# FRONT-UNIT-3_5.net
KiCad netlist of a schematic drawn in Altium Designer
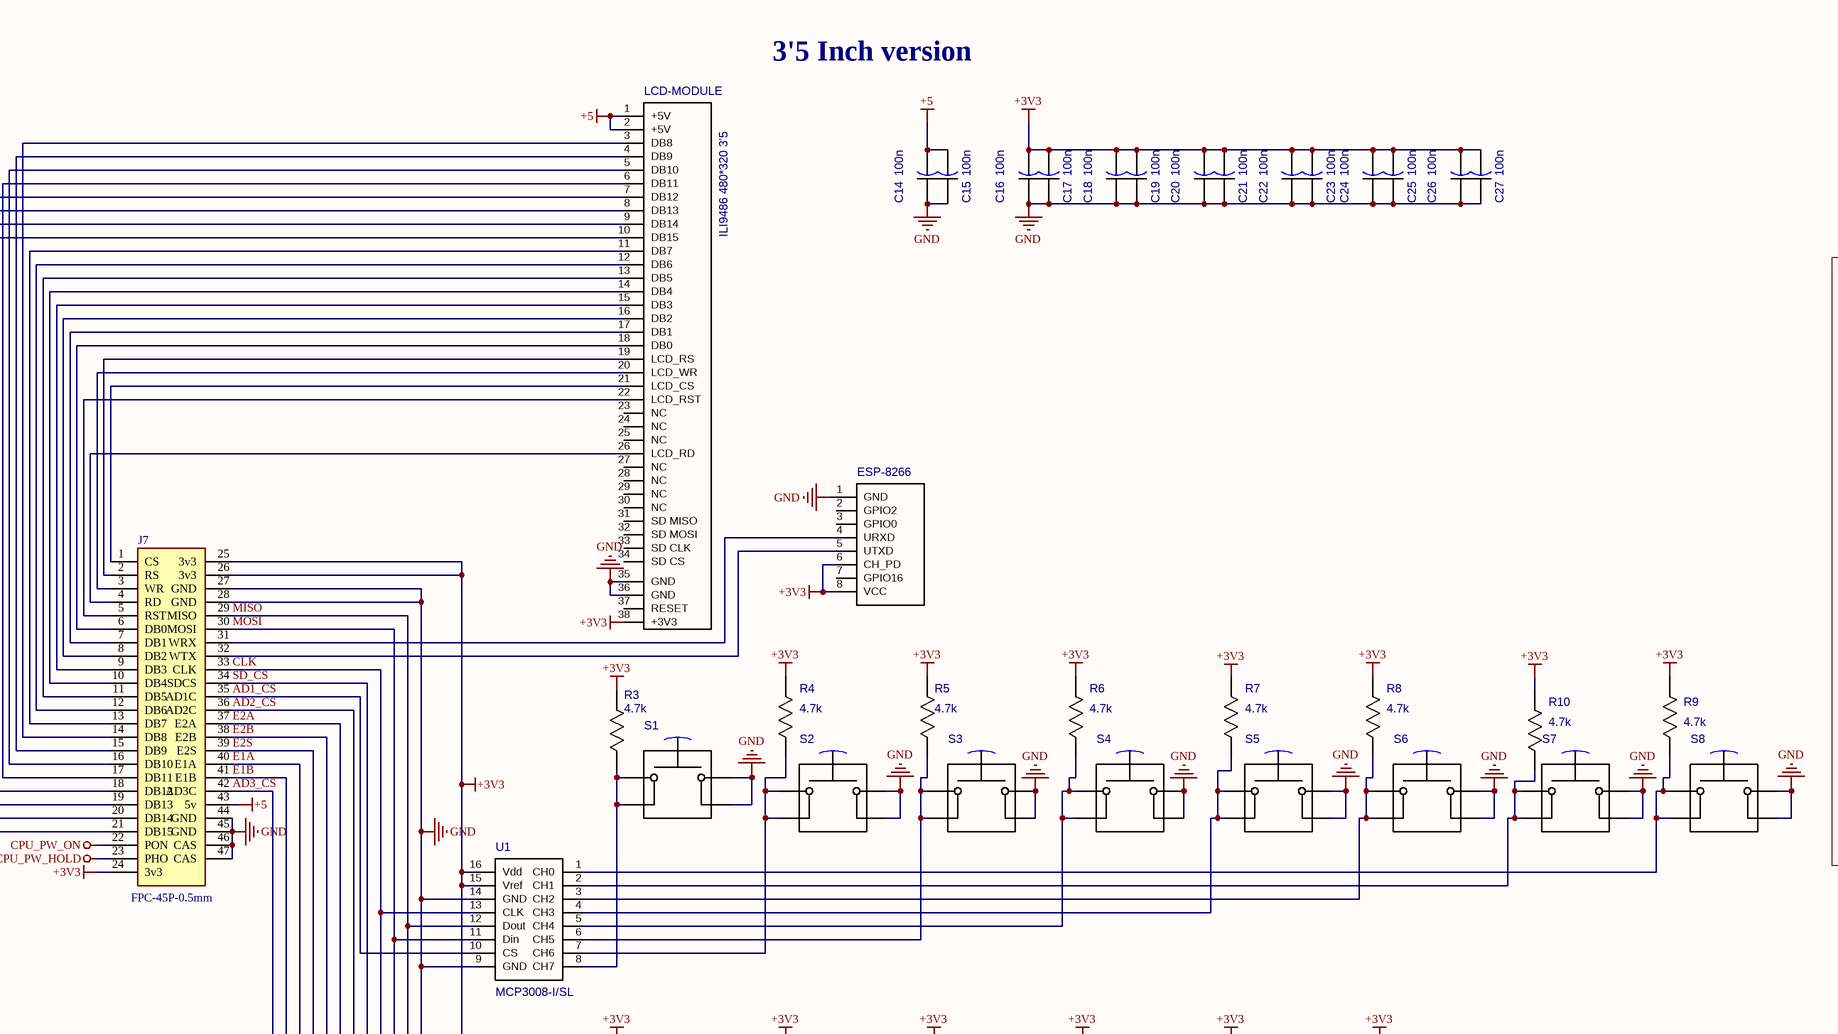
[diagram p0: FRONT-UNIT-3.5.SCHDOC, top left]
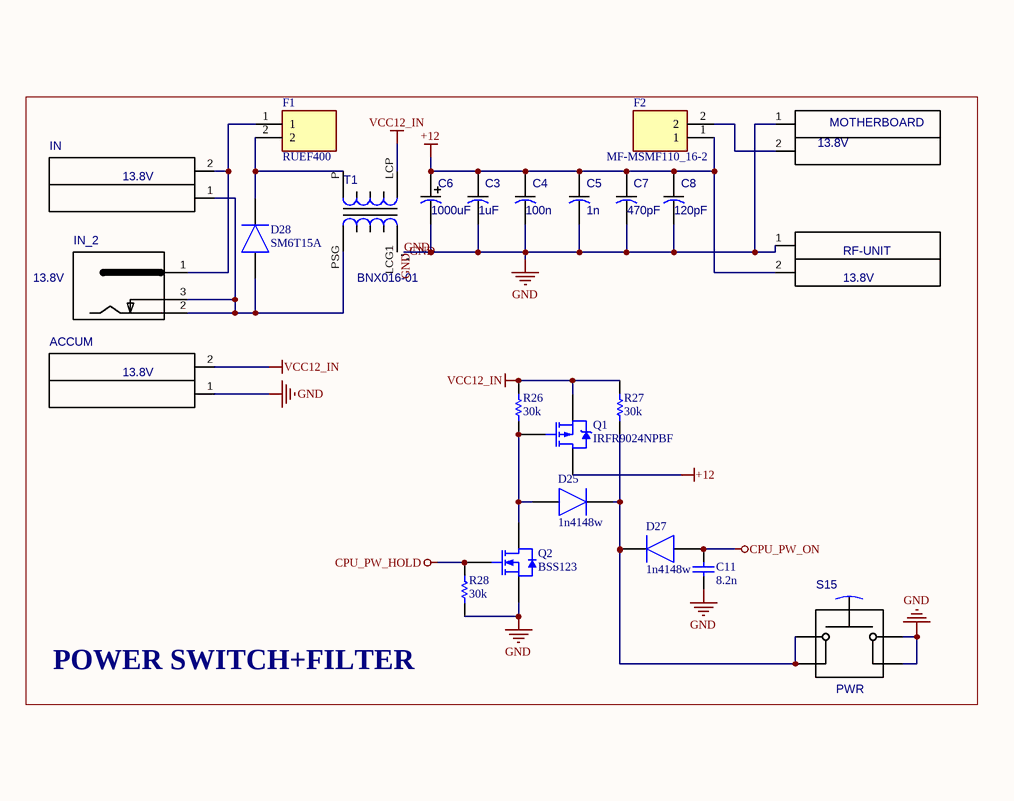
[diagram p1: FRONT-UNIT-3.5.SCHDOC, top right]
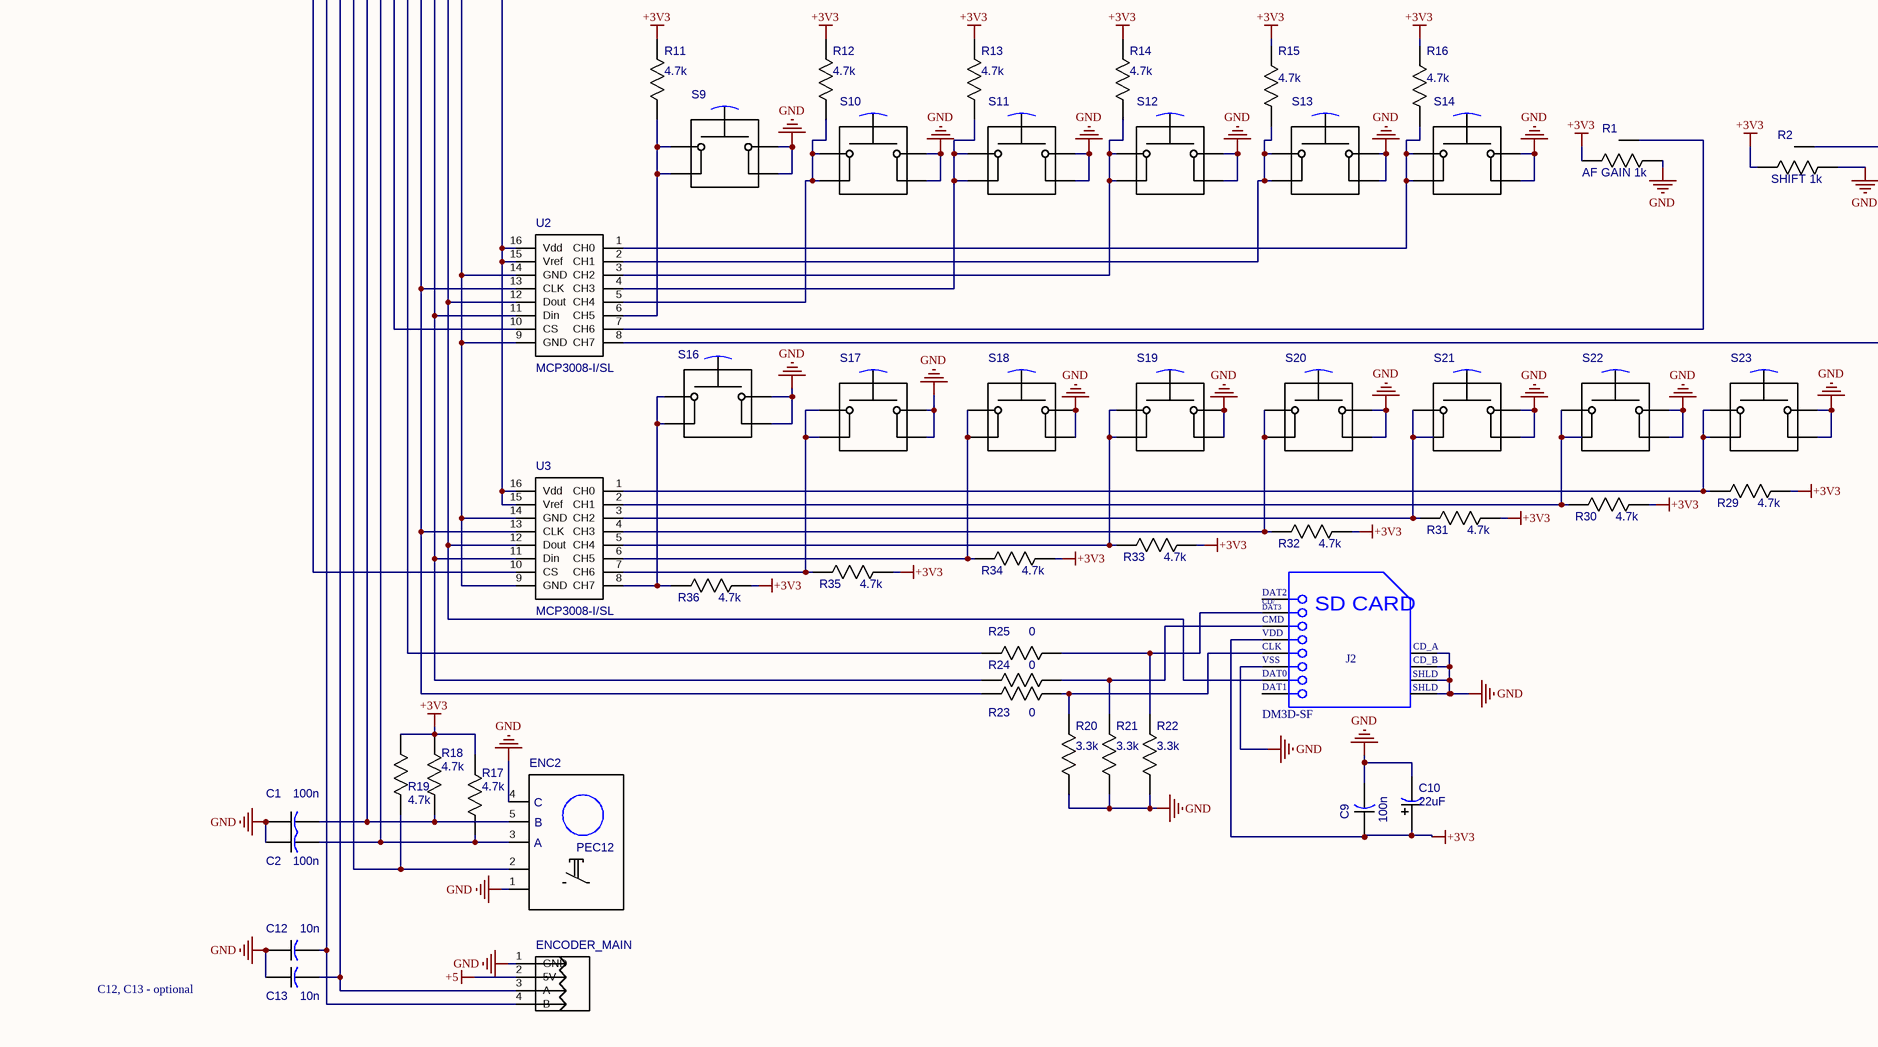
[diagram p2: FRONT-UNIT-3.5.SCHDOC, bottom left]
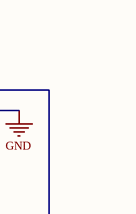
[diagram p3: FRONT-UNIT-3.5.SCHDOC, bottom right]

(export (version "E")
  (design (tool "Eeschema 10.0.6"))
  (components
    (comp (ref "ACCUM")
      (value "13.8V")
      (footprint "JX2")
      (description "JX2")
      (libsource (lib "*") (part "JX2"))
    )
    (comp (ref "C1")
      (value "100n")
      (footprint "CAP_0805")
      (description "CAP_0805")
      (libsource (lib "*") (part "CAP_0805"))
    )
    (comp (ref "C2")
      (value "100n")
      (footprint "CAP_0805")
      (description "CAP_0805")
      (libsource (lib "*") (part "CAP_0805"))
    )
    (comp (ref "C3")
      (value "1uF")
      (footprint "CAP_1206")
      (description "CAP_1206")
      (libsource (lib "*") (part "CAP_1206"))
    )
    (comp (ref "C4")
      (value "100n")
      (footprint "CAP_1206")
      (description "CAP_1206")
      (libsource (lib "*") (part "CAP_1206"))
    )
    (comp (ref "C5")
      (value "1n")
      (footprint "CAP_1206")
      (description "CAP_1206")
      (libsource (lib "*") (part "CAP_1206"))
    )
    (comp (ref "C6")
      (value "1000uF")
      (footprint "CAP250RP")
      (description "CAP250RP")
      (libsource (lib "*") (part "CAP250RP"))
    )
    (comp (ref "C7")
      (value "470pF")
      (footprint "CAP_1206")
      (description "CAP_1206")
      (libsource (lib "*") (part "CAP_1206"))
    )
    (comp (ref "C8")
      (value "120pF")
      (footprint "CAP_1206")
      (description "CAP_1206")
      (libsource (lib "*") (part "CAP_1206"))
    )
    (comp (ref "C9")
      (value "100n")
      (footprint "CAP_0805")
      (description "CAP_0805")
      (libsource (lib "*") (part "CAP_0805"))
    )
    (comp (ref "C10")
      (value "22uF")
      (footprint "EEEFC_sizeB")
      (description "EEEFC_sizeB")
      (libsource (lib "*") (part "EEEFC_sizeB"))
    )
    (comp (ref "C11")
      (value "8.2n")
      (footprint "CAPC2013X94X50LL20T25")
      (description "CAP_1206")
      (fields
        (field (name "MANUFACTURER") "AVX Interconnect / Elco")
        (field (name "PART NUMBER") "08055C822KAT2A")
      )
      (libsource (lib "Altium Content Vault") (part "CAP"))
    )
    (comp (ref "C12")
      (value "10n")
      (footprint "CAP_0805")
      (description "CAP_0805")
      (libsource (lib "*") (part "CAP_0805"))
    )
    (comp (ref "C13")
      (value "10n")
      (footprint "CAP_0805")
      (description "CAP_0805")
      (libsource (lib "*") (part "CAP_0805"))
    )
    (comp (ref "C14")
      (value "100n")
      (footprint "CAP_0805")
      (description "CAP_0805")
      (libsource (lib "*") (part "CAP_0805"))
    )
    (comp (ref "C15")
      (value "100n")
      (footprint "CAP_0805")
      (description "CAP_0805")
      (libsource (lib "*") (part "CAP_0805"))
    )
    (comp (ref "C16")
      (value "100n")
      (footprint "CAP_0805")
      (description "CAP_0805")
      (libsource (lib "*") (part "CAP_0805"))
    )
    (comp (ref "C17")
      (value "100n")
      (footprint "CAP_0805")
      (description "CAP_0805")
      (libsource (lib "*") (part "CAP_0805"))
    )
    (comp (ref "C18")
      (value "100n")
      (footprint "CAP_0805")
      (description "CAP_0805")
      (libsource (lib "*") (part "CAP_0805"))
    )
    (comp (ref "C19")
      (value "100n")
      (footprint "CAP_0805")
      (description "CAP_0805")
      (libsource (lib "*") (part "CAP_0805"))
    )
    (comp (ref "C20")
      (value "100n")
      (footprint "CAP_0805")
      (description "CAP_0805")
      (libsource (lib "*") (part "CAP_0805"))
    )
    (comp (ref "C21")
      (value "100n")
      (footprint "CAP_0805")
      (description "CAP_0805")
      (libsource (lib "*") (part "CAP_0805"))
    )
    (comp (ref "C22")
      (value "100n")
      (footprint "CAP_0805")
      (description "CAP_0805")
      (libsource (lib "*") (part "CAP_0805"))
    )
    (comp (ref "C23")
      (value "100n")
      (footprint "CAP_0805")
      (description "CAP_0805")
      (libsource (lib "*") (part "CAP_0805"))
    )
    (comp (ref "C24")
      (value "100n")
      (footprint "CAP_0805")
      (description "CAP_0805")
      (libsource (lib "*") (part "CAP_0805"))
    )
    (comp (ref "C25")
      (value "100n")
      (footprint "CAP_0805")
      (description "CAP_0805")
      (libsource (lib "*") (part "CAP_0805"))
    )
    (comp (ref "C26")
      (value "100n")
      (footprint "CAP_0805")
      (description "CAP_0805")
      (libsource (lib "*") (part "CAP_0805"))
    )
    (comp (ref "C27")
      (value "100n")
      (footprint "CAP_0805")
      (description "CAP_0805")
      (libsource (lib "*") (part "CAP_0805"))
    )
    (comp (ref "D25")
      (value "1n4148w")
      (footprint "SamacSys:SOD3716X135N")
      (description "Diode")
      (libsource (lib "*") (part "1n4148w"))
    )
    (comp (ref "D27")
      (value "1n4148w")
      (footprint "SamacSys:SOD3716X135N")
      (description "Diode")
      (libsource (lib "*") (part "1n4148w"))
    )
    (comp (ref "D28")
      (value "SM6T15A")
      (footprint "SamacSys:SMBJ36CATR")
      (description "Diode")
      (fields (field (name "MOUSER PART NUMBER") "511-SM6T15A") (field (name "RS PART NUMBER") "4864915P"))
      (libsource (lib "*") (part "SM6T15A"))
    )
    (comp (ref "ENC2") (value "PEC12") (footprint "PEC12") (libsource (lib "*") (part "PEC12")))
    (comp (ref "ENCODER_MAIN")
      (value "OPTICAL ENCODER")
      (footprint "644456-4")
      (libsource (lib "*") (part "644456-4"))
    )
    (comp (ref "ESP-8266")
      (value "ESP-01 ESP8266")
      (footprint "ESP-01 ESP8266")
      (libsource (lib "*") (part "ESP-01 ESP8266"))
    )
    (comp (ref "F1")
      (value "RUEF400")
      (footprint "SamacSys:RUEF400")
      (description "Fuse")
      (fields (field (name "MOUSER PART NUMBER") "650-RUEF400") (field (name "RS PART NUMBER") "5176837P"))
      (libsource (lib "*") (part "RUEF400"))
    )
    (comp (ref "F2")
      (value "MF-MSMF110_16-2")
      (footprint "SamacSys:FUSC4632X85N")
      (description "Fuse")
      (fields
        (field (name "MANUFACTURER_PART_NUMBER") "MF-MSMF110/16-2")
        (field (name "MOUSER PART NUMBER") "652-MF-MSMF110/16-2")
      )
      (libsource (lib "*") (part "MF-MSMF110_16-2"))
    )
    (comp (ref "IN") (value "13.8V") (footprint "JX2") (description "JX2") (libsource (lib "*") (part "JX2")))
    (comp (ref "IN_2")
      (value "13.8V")
      (footprint "PJ-050B")
      (description "PJ-050B")
      (libsource (lib "*") (part "PJ-050B"))
    )
    (comp (ref "J2")
      (value "DM3D-SF")
      (footprint "HIRO-DM3D-SF_V")
      (fields (field (name "MANUFACTURER") "Hirose Electric"))
      (libsource (lib "Altium Content Vault") (part "CN-SD-8-2SW-2S"))
    )
    (comp (ref "J7")
      (value "FPC-45P-0.5mm")
      (footprint "FRONT-UNIT-3.5:FH12S45S05SH60")
      (description "Connector")
      (fields
        (field (name "MANUFACTURER_PART_NUMBER") "FH12S-45S-0.5SH(55)")
        (field (name "MOUSER PART NUMBER") "798-FH12S-45S-05SH55")
      )
      (libsource (lib "*") (part "FH12S-45S-0.5SH_55_"))
    )
    (comp (ref "LCD-MODULE")
      (value "ILI9486 480*320 3'5")
      (footprint "LCD-MODULE-3.2-480-320")
      (description "LCD-MODULE_3'2_480х320")
      (libsource (lib "FRONT-UNIT") (part "LCD-MODULE_3'2_480х320"))
    )
    (comp (ref "MOTHERBOARD")
      (value "13.8V")
      (footprint "JX2")
      (description "JX2")
      (libsource (lib "*") (part "JX2"))
    )
    (comp (ref "Q1")
      (value "IRFR9024NPBF")
      (footprint "ONSC-DPAK-3-369C-01_V")
      (description "IRFR9024NPBF, Транзистор, Р-канал 55В 11А")
      (fields (field (name "MANUFACTURER") "On Semiconductor") (field (name "PARTNUMBER") "NTD2955G"))
      (libsource (lib "Altium Content Vault") (part "ONSC-PMOS-G1S3D4-3_B"))
    )
    (comp (ref "Q2")
      (value "BSS123")
      (footprint "FAIR-SOT23-3_V")
      (fields (field (name "MANUFACTURER") "Fairchild"))
      (libsource (lib "Altium Content Vault") (part "NEMOS-GSD-3"))
    )
    (comp (ref "R1")
      (value "AF GAIN 1k")
      (footprint "PTV09")
      (description "Adjustable Resistor PTV09")
      (fields (field (name "Comment") "ptv09a-4225f-b102"))
      (libsource (lib "*") (part "PTV09"))
    )
    (comp (ref "R2")
      (value "SHIFT 1k")
      (footprint "PTV09")
      (description "Adjustable Resistor PTV09")
      (fields (field (name "Comment") "ptv09a-4225f-b102"))
      (libsource (lib "*") (part "PTV09"))
    )
    (comp (ref "R3")
      (value "4.7k")
      (footprint "RES_0805")
      (description "RES_0805")
      (libsource (lib "*") (part "RES_0805"))
    )
    (comp (ref "R4")
      (value "4.7k")
      (footprint "RES_0805")
      (description "RES_0805")
      (libsource (lib "*") (part "RES_0805"))
    )
    (comp (ref "R5")
      (value "4.7k")
      (footprint "RES_0805")
      (description "RES_0805")
      (libsource (lib "*") (part "RES_0805"))
    )
    (comp (ref "R6")
      (value "4.7k")
      (footprint "RES_0805")
      (description "RES_0805")
      (libsource (lib "*") (part "RES_0805"))
    )
    (comp (ref "R7")
      (value "4.7k")
      (footprint "RES_0805")
      (description "RES_0805")
      (libsource (lib "*") (part "RES_0805"))
    )
    (comp (ref "R8")
      (value "4.7k")
      (footprint "RES_0805")
      (description "RES_0805")
      (libsource (lib "*") (part "RES_0805"))
    )
    (comp (ref "R9")
      (value "4.7k")
      (footprint "RES_0805")
      (description "RES_0805")
      (libsource (lib "*") (part "RES_0805"))
    )
    (comp (ref "R10")
      (value "4.7k")
      (footprint "RES_0805")
      (description "RES_0805")
      (libsource (lib "*") (part "RES_0805"))
    )
    (comp (ref "R11")
      (value "4.7k")
      (footprint "RES_0805")
      (description "RES_0805")
      (libsource (lib "*") (part "RES_0805"))
    )
    (comp (ref "R12")
      (value "4.7k")
      (footprint "RES_0805")
      (description "RES_0805")
      (libsource (lib "*") (part "RES_0805"))
    )
    (comp (ref "R13")
      (value "4.7k")
      (footprint "RES_0805")
      (description "RES_0805")
      (libsource (lib "*") (part "RES_0805"))
    )
    (comp (ref "R14")
      (value "4.7k")
      (footprint "RES_0805")
      (description "RES_0805")
      (libsource (lib "*") (part "RES_0805"))
    )
    (comp (ref "R15")
      (value "4.7k")
      (footprint "RES_0805")
      (description "RES_0805")
      (libsource (lib "*") (part "RES_0805"))
    )
    (comp (ref "R16")
      (value "4.7k")
      (footprint "RES_0805")
      (description "RES_0805")
      (libsource (lib "*") (part "RES_0805"))
    )
    (comp (ref "R17")
      (value "4.7k")
      (footprint "RES_0805")
      (description "RES_0805")
      (libsource (lib "*") (part "RES_0805"))
    )
    (comp (ref "R18")
      (value "4.7k")
      (footprint "RES_0805")
      (description "RES_0805")
      (libsource (lib "*") (part "RES_0805"))
    )
    (comp (ref "R19")
      (value "4.7k")
      (footprint "RES_0805")
      (description "RES_0805")
      (libsource (lib "*") (part "RES_0805"))
    )
    (comp (ref "R20")
      (value "3.3k")
      (footprint "RES_0805")
      (description "RES_0805")
      (libsource (lib "*") (part "RES_0805"))
    )
    (comp (ref "R21")
      (value "3.3k")
      (footprint "RES_0805")
      (description "RES_0805")
      (libsource (lib "*") (part "RES_0805"))
    )
    (comp (ref "R22")
      (value "3.3k")
      (footprint "RES_0805")
      (description "RES_0805")
      (libsource (lib "*") (part "RES_0805"))
    )
    (comp (ref "R23")
      (value "0")
      (footprint "RES_0805")
      (description "RES_0805")
      (libsource (lib "*") (part "RES_0805"))
    )
    (comp (ref "R24")
      (value "0")
      (footprint "RES_0805")
      (description "RES_0805")
      (libsource (lib "*") (part "RES_0805"))
    )
    (comp (ref "R25")
      (value "0")
      (footprint "RES_0805")
      (description "RES_0805")
      (libsource (lib "*") (part "RES_0805"))
    )
    (comp (ref "R26")
      (value "30k")
      (footprint "RESC2013X60X40NL20T25")
      (description "RES_0805")
      (fields (field (name "MANUFACTURER") "Panasonic") (field (name "PART NUMBER") "ERA-6AEB303V"))
      (libsource (lib "Altium Content Vault") (part "RES"))
    )
    (comp (ref "R27")
      (value "30k")
      (footprint "RESC2013X60X40NL20T25")
      (description "RES_0805")
      (fields (field (name "MANUFACTURER") "Panasonic") (field (name "PART NUMBER") "ERA-6AEB303V"))
      (libsource (lib "Altium Content Vault") (part "RES"))
    )
    (comp (ref "R28")
      (value "30k")
      (footprint "RESC2013X60X40NL20T25")
      (description "RES_0805")
      (fields (field (name "MANUFACTURER") "Panasonic") (field (name "PART NUMBER") "ERA-6AEB303V"))
      (libsource (lib "Altium Content Vault") (part "RES"))
    )
    (comp (ref "R29")
      (value "4.7k")
      (footprint "RES_0805")
      (description "RES_0805")
      (libsource (lib "*") (part "RES_0805"))
    )
    (comp (ref "R30")
      (value "4.7k")
      (footprint "RES_0805")
      (description "RES_0805")
      (libsource (lib "*") (part "RES_0805"))
    )
    (comp (ref "R31")
      (value "4.7k")
      (footprint "RES_0805")
      (description "RES_0805")
      (libsource (lib "*") (part "RES_0805"))
    )
    (comp (ref "R32")
      (value "4.7k")
      (footprint "RES_0805")
      (description "RES_0805")
      (libsource (lib "*") (part "RES_0805"))
    )
    (comp (ref "R33")
      (value "4.7k")
      (footprint "RES_0805")
      (description "RES_0805")
      (libsource (lib "*") (part "RES_0805"))
    )
    (comp (ref "R34")
      (value "4.7k")
      (footprint "RES_0805")
      (description "RES_0805")
      (libsource (lib "*") (part "RES_0805"))
    )
    (comp (ref "R35")
      (value "4.7k")
      (footprint "RES_0805")
      (description "RES_0805")
      (libsource (lib "*") (part "RES_0805"))
    )
    (comp (ref "R36")
      (value "4.7k")
      (footprint "RES_0805")
      (description "RES_0805")
      (libsource (lib "*") (part "RES_0805"))
    )
    (comp (ref "RF-UNIT")
      (value "13.8V")
      (footprint "JX2")
      (description "JX2")
      (libsource (lib "*") (part "JX2"))
    )
    (comp (ref "S1")
      (value "PTS645SK50LFS")
      (footprint "PTS645SK50LFS")
      (fields (field (name "LCSC PART #") "test"))
      (libsource (lib "*") (part "PTS645SK50LFS"))
    )
    (comp (ref "S2")
      (value "PTS645SK50LFS")
      (footprint "PTS645SK50LFS")
      (libsource (lib "*") (part "PTS645SK50LFS"))
    )
    (comp (ref "S3")
      (value "PTS645SK50LFS")
      (footprint "PTS645SK50LFS")
      (libsource (lib "*") (part "PTS645SK50LFS"))
    )
    (comp (ref "S4")
      (value "PTS645SK50LFS")
      (footprint "PTS645SK50LFS")
      (libsource (lib "*") (part "PTS645SK50LFS"))
    )
    (comp (ref "S5")
      (value "PTS645SK50LFS")
      (footprint "PTS645SK50LFS")
      (libsource (lib "*") (part "PTS645SK50LFS"))
    )
    (comp (ref "S6")
      (value "PTS645SK50LFS")
      (footprint "PTS645SK50LFS")
      (libsource (lib "*") (part "PTS645SK50LFS"))
    )
    (comp (ref "S7")
      (value "PTS645SK50LFS")
      (footprint "PTS645SK50LFS")
      (libsource (lib "*") (part "PTS645SK50LFS"))
    )
    (comp (ref "S8")
      (value "PTS645SK50LFS")
      (footprint "PTS645SK50LFS")
      (libsource (lib "*") (part "PTS645SK50LFS"))
    )
    (comp (ref "S9")
      (value "PTS645SK50LFS")
      (footprint "PTS645SK50LFS")
      (libsource (lib "*") (part "PTS645SK50LFS"))
    )
    (comp (ref "S10")
      (value "PTS645SK50LFS")
      (footprint "PTS645SK50LFS")
      (libsource (lib "*") (part "PTS645SK50LFS"))
    )
    (comp (ref "S11")
      (value "PTS645SK50LFS")
      (footprint "PTS645SK50LFS")
      (libsource (lib "*") (part "PTS645SK50LFS"))
    )
    (comp (ref "S12")
      (value "PTS645SK50LFS")
      (footprint "PTS645SK50LFS")
      (libsource (lib "*") (part "PTS645SK50LFS"))
    )
    (comp (ref "S13")
      (value "PTS645SK50LFS")
      (footprint "PTS645SK50LFS")
      (libsource (lib "*") (part "PTS645SK50LFS"))
    )
    (comp (ref "S14")
      (value "PTS645SK50LFS")
      (footprint "PTS645SK50LFS")
      (libsource (lib "*") (part "PTS645SK50LFS"))
    )
    (comp (ref "S15")
      (value "PWR")
      (footprint "PTS645SK50LFS")
      (description "PTS645SK50LFS")
      (libsource (lib "*") (part "PTS645SK50LFS"))
    )
    (comp (ref "S16")
      (value "PTS645SK50LFS")
      (footprint "PTS645SK50LFS")
      (libsource (lib "*") (part "PTS645SK50LFS"))
    )
    (comp (ref "S17")
      (value "PTS645SK50LFS")
      (footprint "PTS645SK50LFS")
      (libsource (lib "*") (part "PTS645SK50LFS"))
    )
    (comp (ref "S18")
      (value "PTS645SK50LFS")
      (footprint "PTS645SK50LFS")
      (libsource (lib "*") (part "PTS645SK50LFS"))
    )
    (comp (ref "S19")
      (value "PTS645SK50LFS")
      (footprint "PTS645SK50LFS")
      (libsource (lib "*") (part "PTS645SK50LFS"))
    )
    (comp (ref "S20")
      (value "PTS645SK50LFS")
      (footprint "PTS645SK50LFS")
      (libsource (lib "*") (part "PTS645SK50LFS"))
    )
    (comp (ref "S21")
      (value "PTS645SK50LFS")
      (footprint "PTS645SK50LFS")
      (libsource (lib "*") (part "PTS645SK50LFS"))
    )
    (comp (ref "S22")
      (value "PTS645SK50LFS")
      (footprint "PTS645SK50LFS")
      (libsource (lib "*") (part "PTS645SK50LFS"))
    )
    (comp (ref "S23")
      (value "PTS645SK50LFS")
      (footprint "PTS645SK50LFS")
      (libsource (lib "*") (part "PTS645SK50LFS"))
    )
    (comp (ref "T1")
      (value "BNX016-01")
      (footprint "TRANSF_ICORE")
      (libsource (lib "*") (part "TRANSF_ICORE"))
    )
    (comp (ref "U1")
      (value "MCP3008-I/SL")
      (footprint "MCP3008-I/SL")
      (libsource (lib "*") (part "MCP3008-I/SL"))
    )
    (comp (ref "U2")
      (value "MCP3008-I/SL")
      (footprint "MCP3008-I/SL")
      (libsource (lib "*") (part "MCP3008-I/SL"))
    )
    (comp (ref "U3")
      (value "MCP3008-I/SL")
      (footprint "MCP3008-I/SL")
      (libsource (lib "*") (part "MCP3008-I/SL"))
    )
  )
  (nets
    (net (code "1") (name "+3V3") (class "Default")
      (node (ref "C10") (pin "1") (pinfunction "PLUS_1") (pintype "passive"))
      (node (ref "C16") (pin "2") (pinfunction "2_2") (pintype "passive"))
      (node (ref "C17") (pin "2") (pinfunction "2_2") (pintype "passive"))
      (node (ref "C18") (pin "2") (pinfunction "2_2") (pintype "passive"))
      (node (ref "C19") (pin "2") (pinfunction "2_2") (pintype "passive"))
      (node (ref "C20") (pin "2") (pinfunction "2_2") (pintype "passive"))
      (node (ref "C21") (pin "2") (pinfunction "2_2") (pintype "passive"))
      (node (ref "C22") (pin "2") (pinfunction "2_2") (pintype "passive"))
      (node (ref "C23") (pin "2") (pinfunction "2_2") (pintype "passive"))
      (node (ref "C24") (pin "2") (pinfunction "2_2") (pintype "passive"))
      (node (ref "C25") (pin "2") (pinfunction "2_2") (pintype "passive"))
      (node (ref "C26") (pin "2") (pinfunction "2_2") (pintype "passive"))
      (node (ref "C27") (pin "2") (pinfunction "2_2") (pintype "passive"))
      (node (ref "C9") (pin "1") (pinfunction "1_1") (pintype "passive"))
      (node (ref "ESP-8266") (pin "6") (pinfunction "CH_PD_6") (pintype "passive"))
      (node (ref "ESP-8266") (pin "8") (pinfunction "VCC_8") (pintype "passive"))
      (node (ref "J2") (pin "4") (pinfunction "VDD_4") (pintype "passive"))
      (node (ref "J7") (pin "24") (pinfunction "3v3_24") (pintype "passive"))
      (node (ref "J7") (pin "25") (pinfunction "3v3_25") (pintype "passive"))
      (node (ref "J7") (pin "26") (pinfunction "3v3_26") (pintype "passive"))
      (node (ref "LCD-MODULE") (pin "38") (pinfunction "+3V3_38") (pintype "passive"))
      (node (ref "R1") (pin "1") (pinfunction "CW_1") (pintype "passive"))
      (node (ref "R10") (pin "2") (pinfunction "2_2") (pintype "passive"))
      (node (ref "R11") (pin "2") (pinfunction "2_2") (pintype "passive"))
      (node (ref "R12") (pin "2") (pinfunction "2_2") (pintype "passive"))
      (node (ref "R13") (pin "2") (pinfunction "2_2") (pintype "passive"))
      (node (ref "R14") (pin "2") (pinfunction "2_2") (pintype "passive"))
      (node (ref "R15") (pin "2") (pinfunction "2_2") (pintype "passive"))
      (node (ref "R16") (pin "2") (pinfunction "2_2") (pintype "passive"))
      (node (ref "R17") (pin "2") (pinfunction "2_2") (pintype "passive"))
      (node (ref "R18") (pin "2") (pinfunction "2_2") (pintype "passive"))
      (node (ref "R19") (pin "2") (pinfunction "2_2") (pintype "passive"))
      (node (ref "R2") (pin "1") (pinfunction "CW_1") (pintype "passive"))
      (node (ref "R29") (pin "2") (pinfunction "2_2") (pintype "passive"))
      (node (ref "R3") (pin "2") (pinfunction "2_2") (pintype "passive"))
      (node (ref "R30") (pin "2") (pinfunction "2_2") (pintype "passive"))
      (node (ref "R31") (pin "2") (pinfunction "2_2") (pintype "passive"))
      (node (ref "R32") (pin "2") (pinfunction "2_2") (pintype "passive"))
      (node (ref "R33") (pin "2") (pinfunction "2_2") (pintype "passive"))
      (node (ref "R34") (pin "2") (pinfunction "2_2") (pintype "passive"))
      (node (ref "R35") (pin "2") (pinfunction "2_2") (pintype "passive"))
      (node (ref "R36") (pin "2") (pinfunction "2_2") (pintype "passive"))
      (node (ref "R4") (pin "2") (pinfunction "2_2") (pintype "passive"))
      (node (ref "R5") (pin "2") (pinfunction "2_2") (pintype "passive"))
      (node (ref "R6") (pin "2") (pinfunction "2_2") (pintype "passive"))
      (node (ref "R7") (pin "2") (pinfunction "2_2") (pintype "passive"))
      (node (ref "R8") (pin "2") (pinfunction "2_2") (pintype "passive"))
      (node (ref "R9") (pin "2") (pinfunction "2_2") (pintype "passive"))
      (node (ref "U1") (pin "15") (pinfunction "Vref_15") (pintype "passive"))
      (node (ref "U1") (pin "16") (pinfunction "Vdd_16") (pintype "passive"))
      (node (ref "U2") (pin "15") (pinfunction "Vref_15") (pintype "passive"))
      (node (ref "U2") (pin "16") (pinfunction "Vdd_16") (pintype "passive"))
      (node (ref "U3") (pin "15") (pinfunction "Vref_15") (pintype "passive"))
      (node (ref "U3") (pin "16") (pinfunction "Vdd_16") (pintype "passive"))
    )
    (net (code "2") (name "+5") (class "Default")
      (node (ref "C14") (pin "2") (pinfunction "2_2") (pintype "passive"))
      (node (ref "C15") (pin "2") (pinfunction "2_2") (pintype "passive"))
      (node (ref "ENCODER_MAIN") (pin "2") (pinfunction "5V_2") (pintype "passive"))
      (node (ref "J7") (pin "43") (pinfunction "5v_43") (pintype "passive"))
      (node (ref "LCD-MODULE") (pin "1") (pinfunction "+5V_1") (pintype "passive"))
      (node (ref "LCD-MODULE") (pin "2") (pinfunction "+5V_2") (pintype "passive"))
    )
    (net (code "3") (name "+12") (class "Default")
      (node (ref "C3") (pin "1") (pinfunction "1_1") (pintype "passive"))
      (node (ref "C4") (pin "1") (pinfunction "1_1") (pintype "passive"))
      (node (ref "C5") (pin "1") (pinfunction "1_1") (pintype "passive"))
      (node (ref "C6") (pin "1") (pinfunction "PLUS_1") (pintype "passive"))
      (node (ref "C7") (pin "1") (pinfunction "1_1") (pintype "passive"))
      (node (ref "C8") (pin "1") (pinfunction "1_1") (pintype "passive"))
      (node (ref "F2") (pin "1") (pinfunction "1_1") (pintype "passive"))
      (node (ref "Q1") (pin "4") (pinfunction "D_4") (pintype "passive"))
      (node (ref "RF-UNIT") (pin "2") (pinfunction "1_2") (pintype "passive"))
    )
    (net (code "4") (name "/AD1_CS") (class "Default")
      (node (ref "J7") (pin "35") (pinfunction "AD1C_35") (pintype "passive"))
      (node (ref "U1") (pin "10") (pinfunction "CS_10") (pintype "passive"))
    )
    (net (code "5") (name "/AD2_CS") (class "Default")
      (node (ref "J7") (pin "36") (pinfunction "AD2C_36") (pintype "passive"))
      (node (ref "U2") (pin "10") (pinfunction "CS_10") (pintype "passive"))
    )
    (net (code "6") (name "/AD3_CS") (class "Default")
      (node (ref "J7") (pin "42") (pinfunction "AD3C_42") (pintype "passive"))
      (node (ref "U3") (pin "10") (pinfunction "CS_10") (pintype "passive"))
    )
    (net (code "7") (name "/CLK") (class "Default")
      (node (ref "J7") (pin "33") (pinfunction "CLK_33") (pintype "passive"))
      (node (ref "R23") (pin "2") (pinfunction "2_2") (pintype "passive"))
      (node (ref "U1") (pin "13") (pinfunction "CLK_13") (pintype "passive"))
      (node (ref "U2") (pin "13") (pinfunction "CLK_13") (pintype "passive"))
      (node (ref "U3") (pin "13") (pinfunction "CLK_13") (pintype "passive"))
    )
    (net (code "8") (name "/E1A") (class "Default")
      (node (ref "C13") (pin "2") (pinfunction "2_2") (pintype "passive"))
      (node (ref "ENCODER_MAIN") (pin "3") (pinfunction "A_3") (pintype "passive"))
      (node (ref "J7") (pin "40") (pinfunction "E1A_40") (pintype "passive"))
    )
    (net (code "9") (name "/E1B") (class "Default")
      (node (ref "C12") (pin "2") (pinfunction "2_2") (pintype "passive"))
      (node (ref "ENCODER_MAIN") (pin "4") (pinfunction "B_4") (pintype "passive"))
      (node (ref "J7") (pin "41") (pinfunction "E1B_41") (pintype "passive"))
    )
    (net (code "10") (name "/E2A") (class "Default")
      (node (ref "C2") (pin "2") (pinfunction "2_2") (pintype "passive"))
      (node (ref "ENC2") (pin "3") (pinfunction "A_3") (pintype "passive"))
      (node (ref "J7") (pin "37") (pinfunction "E2A_37") (pintype "passive"))
      (node (ref "R17") (pin "1") (pinfunction "1_1") (pintype "passive"))
    )
    (net (code "11") (name "/E2B") (class "Default")
      (node (ref "C1") (pin "2") (pinfunction "2_2") (pintype "passive"))
      (node (ref "ENC2") (pin "5") (pinfunction "B_5") (pintype "passive"))
      (node (ref "J7") (pin "38") (pinfunction "E2B_38") (pintype "passive"))
      (node (ref "R18") (pin "1") (pinfunction "1_1") (pintype "passive"))
    )
    (net (code "12") (name "/E2S") (class "Default")
      (node (ref "ENC2") (pin "2") (pinfunction "2_2") (pintype "passive"))
      (node (ref "J7") (pin "39") (pinfunction "E2S_39") (pintype "passive"))
      (node (ref "R19") (pin "1") (pinfunction "1_1") (pintype "passive"))
    )
    (net (code "13") (name "/MISO") (class "Default")
      (node (ref "J2") (pin "7") (pinfunction "DAT0_7") (pintype "passive"))
      (node (ref "J7") (pin "29") (pinfunction "MISO_29") (pintype "passive"))
      (node (ref "U1") (pin "12") (pinfunction "Dout_12") (pintype "passive"))
      (node (ref "U2") (pin "12") (pinfunction "Dout_12") (pintype "passive"))
      (node (ref "U3") (pin "12") (pinfunction "Dout_12") (pintype "passive"))
    )
    (net (code "14") (name "/MOSI") (class "Default")
      (node (ref "J7") (pin "30") (pinfunction "MOSI_30") (pintype "passive"))
      (node (ref "R24") (pin "2") (pinfunction "2_2") (pintype "passive"))
      (node (ref "U1") (pin "11") (pinfunction "Din_11") (pintype "passive"))
      (node (ref "U2") (pin "11") (pinfunction "Din_11") (pintype "passive"))
      (node (ref "U3") (pin "11") (pinfunction "Din_11") (pintype "passive"))
    )
    (net (code "15") (name "/SD_CS") (class "Default")
      (node (ref "J7") (pin "34") (pinfunction "SDCS_34") (pintype "passive"))
      (node (ref "R25") (pin "2") (pinfunction "2_2") (pintype "passive"))
    )
    (net (code "16") (name "CPU_PW_HOLD") (class "Default")
      (node (ref "J7") (pin "23") (pinfunction "PHO_23") (pintype "passive"))
      (node (ref "Q2") (pin "1") (pinfunction "G_1") (pintype "passive"))
      (node (ref "R28") (pin "2") (pinfunction "2_2") (pintype "passive"))
    )
    (net (code "17") (name "CPU_PW_ON") (class "Default")
      (node (ref "C11") (pin "2") (pinfunction "2_2") (pintype "passive"))
      (node (ref "D27") (pin "2") (pinfunction "A_2") (pintype "passive"))
      (node (ref "J7") (pin "22") (pinfunction "PON_22") (pintype "passive"))
    )
    (net (code "18") (name "GND") (class "Default")
      (node (ref "ACCUM") (pin "1") (pinfunction "2_1") (pintype "passive"))
      (node (ref "C1") (pin "1") (pinfunction "1_1") (pintype "passive"))
      (node (ref "C10") (pin "2") (pinfunction "MINUS_2") (pintype "passive"))
      (node (ref "C11") (pin "1") (pinfunction "1_1") (pintype "passive"))
      (node (ref "C12") (pin "1") (pinfunction "1_1") (pintype "passive"))
      (node (ref "C13") (pin "1") (pinfunction "1_1") (pintype "passive"))
      (node (ref "C14") (pin "1") (pinfunction "1_1") (pintype "passive"))
      (node (ref "C15") (pin "1") (pinfunction "1_1") (pintype "passive"))
      (node (ref "C16") (pin "1") (pinfunction "1_1") (pintype "passive"))
      (node (ref "C17") (pin "1") (pinfunction "1_1") (pintype "passive"))
      (node (ref "C18") (pin "1") (pinfunction "1_1") (pintype "passive"))
      (node (ref "C19") (pin "1") (pinfunction "1_1") (pintype "passive"))
      (node (ref "C2") (pin "1") (pinfunction "1_1") (pintype "passive"))
      (node (ref "C20") (pin "1") (pinfunction "1_1") (pintype "passive"))
      (node (ref "C21") (pin "1") (pinfunction "1_1") (pintype "passive"))
      (node (ref "C22") (pin "1") (pinfunction "1_1") (pintype "passive"))
      (node (ref "C23") (pin "1") (pinfunction "1_1") (pintype "passive"))
      (node (ref "C24") (pin "1") (pinfunction "1_1") (pintype "passive"))
      (node (ref "C25") (pin "1") (pinfunction "1_1") (pintype "passive"))
      (node (ref "C26") (pin "1") (pinfunction "1_1") (pintype "passive"))
      (node (ref "C27") (pin "1") (pinfunction "1_1") (pintype "passive"))
      (node (ref "C3") (pin "2") (pinfunction "2_2") (pintype "passive"))
      (node (ref "C4") (pin "2") (pinfunction "2_2") (pintype "passive"))
      (node (ref "C5") (pin "2") (pinfunction "2_2") (pintype "passive"))
      (node (ref "C6") (pin "2") (pinfunction "MINUS_2") (pintype "passive"))
      (node (ref "C7") (pin "2") (pinfunction "2_2") (pintype "passive"))
      (node (ref "C8") (pin "2") (pinfunction "2_2") (pintype "passive"))
      (node (ref "C9") (pin "2") (pinfunction "2_2") (pintype "passive"))
      (node (ref "ENC2") (pin "1") (pinfunction "1_1") (pintype "passive"))
      (node (ref "ENC2") (pin "4") (pinfunction "C_4") (pintype "passive"))
      (node (ref "ENCODER_MAIN") (pin "1") (pinfunction "GND_1") (pintype "passive"))
      (node (ref "ESP-8266") (pin "1") (pinfunction "GND_1") (pintype "passive"))
      (node (ref "J2") (pin "10") (pinfunction "CD_B_10") (pintype "passive"))
      (node (ref "J2") (pin "11") (pinfunction "SHLD1_11") (pintype "passive"))
      (node (ref "J2") (pin "12") (pinfunction "SHLD2_12") (pintype "passive"))
      (node (ref "J2") (pin "13") (pinfunction "SHLD3_13") (pintype "passive"))
      (node (ref "J2") (pin "14") (pinfunction "SHLD4_14") (pintype "passive"))
      (node (ref "J2") (pin "6") (pinfunction "VSS2_6") (pintype "passive"))
      (node (ref "J2") (pin "9") (pinfunction "CD_A_9") (pintype "passive"))
      (node (ref "J7") (pin "27") (pinfunction "GND_27") (pintype "passive"))
      (node (ref "J7") (pin "28") (pinfunction "GND_28") (pintype "passive"))
      (node (ref "J7") (pin "44") (pinfunction "GND_44") (pintype "passive"))
      (node (ref "J7") (pin "45") (pinfunction "GND_45") (pintype "passive"))
      (node (ref "J7") (pin "46") (pinfunction "CAS_46") (pintype "passive"))
      (node (ref "J7") (pin "47") (pinfunction "CAS_47") (pintype "passive"))
      (node (ref "LCD-MODULE") (pin "35") (pinfunction "GND_35") (pintype "passive"))
      (node (ref "LCD-MODULE") (pin "36") (pinfunction "GND_36") (pintype "passive"))
      (node (ref "MOTHERBOARD") (pin "1") (pinfunction "2_1") (pintype "passive"))
      (node (ref "Q2") (pin "2") (pinfunction "S_2") (pintype "passive"))
      (node (ref "R1") (pin "3") (pinfunction "CCW_3") (pintype "passive"))
      (node (ref "R2") (pin "3") (pinfunction "CCW_3") (pintype "passive"))
      (node (ref "R20") (pin "1") (pinfunction "1_1") (pintype "passive"))
      (node (ref "R21") (pin "1") (pinfunction "1_1") (pintype "passive"))
      (node (ref "R22") (pin "1") (pinfunction "1_1") (pintype "passive"))
      (node (ref "R28") (pin "1") (pinfunction "1_1") (pintype "passive"))
      (node (ref "RF-UNIT") (pin "1") (pinfunction "2_1") (pintype "passive"))
      (node (ref "S1") (pin "3") (pinfunction "B_3") (pintype "passive"))
      (node (ref "S1") (pin "4") (pinfunction "B_4") (pintype "passive"))
      (node (ref "S10") (pin "3") (pinfunction "B_3") (pintype "passive"))
      (node (ref "S10") (pin "4") (pinfunction "B_4") (pintype "passive"))
      (node (ref "S11") (pin "3") (pinfunction "B_3") (pintype "passive"))
      (node (ref "S11") (pin "4") (pinfunction "B_4") (pintype "passive"))
      (node (ref "S12") (pin "3") (pinfunction "B_3") (pintype "passive"))
      (node (ref "S12") (pin "4") (pinfunction "B_4") (pintype "passive"))
      (node (ref "S13") (pin "3") (pinfunction "B_3") (pintype "passive"))
      (node (ref "S13") (pin "4") (pinfunction "B_4") (pintype "passive"))
      (node (ref "S14") (pin "3") (pinfunction "B_3") (pintype "passive"))
      (node (ref "S14") (pin "4") (pinfunction "B_4") (pintype "passive"))
      (node (ref "S15") (pin "3") (pinfunction "B_3") (pintype "passive"))
      (node (ref "S15") (pin "4") (pinfunction "B_4") (pintype "passive"))
      (node (ref "S16") (pin "3") (pinfunction "B_3") (pintype "passive"))
      (node (ref "S16") (pin "4") (pinfunction "B_4") (pintype "passive"))
      (node (ref "S17") (pin "3") (pinfunction "B_3") (pintype "passive"))
      (node (ref "S17") (pin "4") (pinfunction "B_4") (pintype "passive"))
      (node (ref "S18") (pin "3") (pinfunction "B_3") (pintype "passive"))
      (node (ref "S18") (pin "4") (pinfunction "B_4") (pintype "passive"))
      (node (ref "S19") (pin "3") (pinfunction "B_3") (pintype "passive"))
      (node (ref "S19") (pin "4") (pinfunction "B_4") (pintype "passive"))
      (node (ref "S2") (pin "3") (pinfunction "B_3") (pintype "passive"))
      (node (ref "S2") (pin "4") (pinfunction "B_4") (pintype "passive"))
      (node (ref "S20") (pin "3") (pinfunction "B_3") (pintype "passive"))
      (node (ref "S20") (pin "4") (pinfunction "B_4") (pintype "passive"))
      (node (ref "S21") (pin "3") (pinfunction "B_3") (pintype "passive"))
      (node (ref "S21") (pin "4") (pinfunction "B_4") (pintype "passive"))
      (node (ref "S22") (pin "3") (pinfunction "B_3") (pintype "passive"))
      (node (ref "S22") (pin "4") (pinfunction "B_4") (pintype "passive"))
      (node (ref "S23") (pin "3") (pinfunction "B_3") (pintype "passive"))
      (node (ref "S23") (pin "4") (pinfunction "B_4") (pintype "passive"))
      (node (ref "S3") (pin "3") (pinfunction "B_3") (pintype "passive"))
      (node (ref "S3") (pin "4") (pinfunction "B_4") (pintype "passive"))
      (node (ref "S4") (pin "3") (pinfunction "B_3") (pintype "passive"))
      (node (ref "S4") (pin "4") (pinfunction "B_4") (pintype "passive"))
      (node (ref "S5") (pin "3") (pinfunction "B_3") (pintype "passive"))
      (node (ref "S5") (pin "4") (pinfunction "B_4") (pintype "passive"))
      (node (ref "S6") (pin "3") (pinfunction "B_3") (pintype "passive"))
      (node (ref "S6") (pin "4") (pinfunction "B_4") (pintype "passive"))
      (node (ref "S7") (pin "3") (pinfunction "B_3") (pintype "passive"))
      (node (ref "S7") (pin "4") (pinfunction "B_4") (pintype "passive"))
      (node (ref "S8") (pin "3") (pinfunction "B_3") (pintype "passive"))
      (node (ref "S8") (pin "4") (pinfunction "B_4") (pintype "passive"))
      (node (ref "S9") (pin "3") (pinfunction "B_3") (pintype "passive"))
      (node (ref "S9") (pin "4") (pinfunction "B_4") (pintype "passive"))
      (node (ref "T1") (pin "LCG1") (pinfunction "S2_LCG1") (pintype "passive"))
      (node (ref "T1") (pin "LCG2") (pinfunction "0_LCG2") (pintype "passive"))
      (node (ref "T1") (pin "LCG3") (pinfunction "0_LCG3") (pintype "passive"))
      (node (ref "U1") (pin "14") (pinfunction "GND_14") (pintype "passive"))
      (node (ref "U1") (pin "9") (pinfunction "GND_9") (pintype "passive"))
      (node (ref "U2") (pin "14") (pinfunction "GND_14") (pintype "passive"))
      (node (ref "U2") (pin "9") (pinfunction "GND_9") (pintype "passive"))
      (node (ref "U3") (pin "14") (pinfunction "GND_14") (pintype "passive"))
      (node (ref "U3") (pin "9") (pinfunction "GND_9") (pintype "passive"))
    )
    (net (code "19") (name "Net-(D25-A)") (class "Default")
      (node (ref "D25") (pin "2") (pinfunction "A_2") (pintype "passive"))
      (node (ref "Q1") (pin "1") (pinfunction "G_1") (pintype "passive"))
      (node (ref "Q2") (pin "3") (pinfunction "D_3") (pintype "passive"))
      (node (ref "R26") (pin "1") (pinfunction "1_1") (pintype "passive"))
    )
    (net (code "20") (name "Net-(D25-K)") (class "Default")
      (node (ref "D25") (pin "1") (pinfunction "K_1") (pintype "passive"))
      (node (ref "D27") (pin "1") (pinfunction "K_1") (pintype "passive"))
      (node (ref "R27") (pin "1") (pinfunction "1_1") (pintype "passive"))
      (node (ref "S15") (pin "1") (pinfunction "A_1") (pintype "passive"))
      (node (ref "S15") (pin "2") (pinfunction "A_2") (pintype "passive"))
    )
    (net (code "21") (name "Net-(D28-A)") (class "Default")
      (node (ref "D28") (pin "2") (pinfunction "A_2") (pintype "passive"))
      (node (ref "IN") (pin "1") (pinfunction "2_1") (pintype "passive"))
      (node (ref "IN_2") (pin "2") (pinfunction "2_2") (pintype "passive"))
      (node (ref "IN_2") (pin "3") (pinfunction "3_3") (pintype "passive"))
      (node (ref "T1") (pin "PSG") (pinfunction "S1_PSG") (pintype "passive"))
    )
    (net (code "22") (name "Net-(D28-K)") (class "Default")
      (node (ref "D28") (pin "1") (pinfunction "K_1") (pintype "passive"))
      (node (ref "F1") (pin "2") (pinfunction "2_2") (pintype "passive"))
      (node (ref "T1") (pin "P") (pinfunction "P1_P") (pintype "passive"))
    )
    (net (code "23") (name "Net-(ESP-8266-URXD)") (class "Default")
      (node (ref "ESP-8266") (pin "4") (pinfunction "URXD_4") (pintype "passive"))
      (node (ref "J7") (pin "31") (pinfunction "WRX_31") (pintype "passive"))
    )
    (net (code "24") (name "Net-(ESP-8266-UTXD)") (class "Default")
      (node (ref "ESP-8266") (pin "5") (pinfunction "UTXD_5") (pintype "passive"))
      (node (ref "J7") (pin "32") (pinfunction "WTX_32") (pintype "passive"))
    )
    (net (code "25") (name "Net-(IN-1)") (class "Default")
      (node (ref "F1") (pin "1") (pinfunction "1_1") (pintype "passive"))
      (node (ref "IN") (pin "2") (pinfunction "1_2") (pintype "passive"))
      (node (ref "IN_2") (pin "1") (pinfunction "1_1") (pintype "passive"))
    )
    (net (code "26") (name "Net-(J2-CLK)") (class "Default")
      (node (ref "J2") (pin "5") (pinfunction "CLK_5") (pintype "passive"))
      (node (ref "R20") (pin "2") (pinfunction "2_2") (pintype "passive"))
      (node (ref "R23") (pin "1") (pinfunction "1_1") (pintype "passive"))
    )
    (net (code "27") (name "Net-(J2-CMD)") (class "Default")
      (node (ref "J2") (pin "2") (pinfunction "CMD_2") (pintype "passive"))
      (node (ref "R22") (pin "2") (pinfunction "2_2") (pintype "passive"))
      (node (ref "R25") (pin "1") (pinfunction "1_1") (pintype "passive"))
    )
    (net (code "28") (name "Net-(J2-VSS1)") (class "Default")
      (node (ref "J2") (pin "3") (pinfunction "VSS1_3") (pintype "passive"))
      (node (ref "R21") (pin "2") (pinfunction "2_2") (pintype "passive"))
      (node (ref "R24") (pin "1") (pinfunction "1_1") (pintype "passive"))
    )
    (net (code "29") (name "Net-(J7-CS)") (class "Default")
      (node (ref "J7") (pin "1") (pinfunction "CS_1") (pintype "passive"))
      (node (ref "LCD-MODULE") (pin "21") (pinfunction "LCD_CS_21") (pintype "passive"))
    )
    (net (code "30") (name "Net-(J7-DB0)") (class "Default")
      (node (ref "J7") (pin "6") (pinfunction "DB0_6") (pintype "passive"))
      (node (ref "LCD-MODULE") (pin "18") (pinfunction "DB0_18") (pintype "passive"))
    )
    (net (code "31") (name "Net-(J7-DB1)") (class "Default")
      (node (ref "J7") (pin "7") (pinfunction "DB1_7") (pintype "passive"))
      (node (ref "LCD-MODULE") (pin "17") (pinfunction "DB1_17") (pintype "passive"))
    )
    (net (code "32") (name "Net-(J7-DB2)") (class "Default")
      (node (ref "J7") (pin "8") (pinfunction "DB2_8") (pintype "passive"))
      (node (ref "LCD-MODULE") (pin "16") (pinfunction "DB2_16") (pintype "passive"))
    )
    (net (code "33") (name "Net-(J7-DB3)") (class "Default")
      (node (ref "J7") (pin "9") (pinfunction "DB3_9") (pintype "passive"))
      (node (ref "LCD-MODULE") (pin "15") (pinfunction "DB3_15") (pintype "passive"))
    )
    (net (code "34") (name "Net-(J7-DB4)") (class "Default")
      (node (ref "J7") (pin "10") (pinfunction "DB4_10") (pintype "passive"))
      (node (ref "LCD-MODULE") (pin "14") (pinfunction "DB4_14") (pintype "passive"))
    )
    (net (code "35") (name "Net-(J7-DB5)") (class "Default")
      (node (ref "J7") (pin "11") (pinfunction "DB5_11") (pintype "passive"))
      (node (ref "LCD-MODULE") (pin "13") (pinfunction "DB5_13") (pintype "passive"))
    )
    (net (code "36") (name "Net-(J7-DB6)") (class "Default")
      (node (ref "J7") (pin "12") (pinfunction "DB6_12") (pintype "passive"))
      (node (ref "LCD-MODULE") (pin "12") (pinfunction "DB6_12") (pintype "passive"))
    )
    (net (code "37") (name "Net-(J7-DB7)") (class "Default")
      (node (ref "J7") (pin "13") (pinfunction "DB7_13") (pintype "passive"))
      (node (ref "LCD-MODULE") (pin "11") (pinfunction "DB7_11") (pintype "passive"))
    )
    (net (code "38") (name "Net-(J7-DB8)") (class "Default")
      (node (ref "J7") (pin "14") (pinfunction "DB8_14") (pintype "passive"))
      (node (ref "LCD-MODULE") (pin "3") (pinfunction "DB8_3") (pintype "passive"))
    )
    (net (code "39") (name "Net-(J7-DB9)") (class "Default")
      (node (ref "J7") (pin "15") (pinfunction "DB9_15") (pintype "passive"))
      (node (ref "LCD-MODULE") (pin "4") (pinfunction "DB9_4") (pintype "passive"))
    )
    (net (code "40") (name "Net-(J7-DB10)") (class "Default")
      (node (ref "J7") (pin "16") (pinfunction "DB10_16") (pintype "passive"))
      (node (ref "LCD-MODULE") (pin "5") (pinfunction "DB10_5") (pintype "passive"))
    )
    (net (code "41") (name "Net-(J7-DB11)") (class "Default")
      (node (ref "J7") (pin "17") (pinfunction "DB11_17") (pintype "passive"))
      (node (ref "LCD-MODULE") (pin "6") (pinfunction "DB11_6") (pintype "passive"))
    )
    (net (code "42") (name "Net-(J7-DB12)") (class "Default")
      (node (ref "J7") (pin "18") (pinfunction "DB12_18") (pintype "passive"))
      (node (ref "LCD-MODULE") (pin "7") (pinfunction "DB12_7") (pintype "passive"))
    )
    (net (code "43") (name "Net-(J7-DB13)") (class "Default")
      (node (ref "J7") (pin "19") (pinfunction "DB13_19") (pintype "passive"))
      (node (ref "LCD-MODULE") (pin "8") (pinfunction "DB13_8") (pintype "passive"))
    )
    (net (code "44") (name "Net-(J7-DB14)") (class "Default")
      (node (ref "J7") (pin "20") (pinfunction "DB14_20") (pintype "passive"))
      (node (ref "LCD-MODULE") (pin "9") (pinfunction "DB14_9") (pintype "passive"))
    )
    (net (code "45") (name "Net-(J7-DB15)") (class "Default")
      (node (ref "J7") (pin "21") (pinfunction "DB15_21") (pintype "passive"))
      (node (ref "LCD-MODULE") (pin "10") (pinfunction "DB15_10") (pintype "passive"))
    )
    (net (code "46") (name "Net-(J7-RD)") (class "Default")
      (node (ref "J7") (pin "4") (pinfunction "RD_4") (pintype "passive"))
      (node (ref "LCD-MODULE") (pin "26") (pinfunction "LCD_RD_26") (pintype "passive"))
    )
    (net (code "47") (name "Net-(J7-RS)") (class "Default")
      (node (ref "J7") (pin "2") (pinfunction "RS_2") (pintype "passive"))
      (node (ref "LCD-MODULE") (pin "19") (pinfunction "LCD_RS_19") (pintype "passive"))
    )
    (net (code "48") (name "Net-(J7-RST)") (class "Default")
      (node (ref "J7") (pin "5") (pinfunction "RST_5") (pintype "passive"))
      (node (ref "LCD-MODULE") (pin "22") (pinfunction "LCD_RST_22") (pintype "passive"))
    )
    (net (code "49") (name "Net-(J7-WR)") (class "Default")
      (node (ref "J7") (pin "3") (pinfunction "WR_3") (pintype "passive"))
      (node (ref "LCD-MODULE") (pin "20") (pinfunction "LCD_WR_20") (pintype "passive"))
    )
    (net (code "50") (name "Net-(MOTHERBOARD-1)") (class "Default")
      (node (ref "F2") (pin "2") (pinfunction "2_2") (pintype "passive"))
      (node (ref "MOTHERBOARD") (pin "2") (pinfunction "1_2") (pintype "passive"))
    )
    (net (code "51") (name "Net-(R1-W)") (class "Default")
      (node (ref "R1") (pin "2") (pinfunction "W_2") (pintype "passive"))
      (node (ref "U2") (pin "7") (pinfunction "CH6_7") (pintype "passive"))
    )
    (net (code "52") (name "Net-(R2-W)") (class "Default")
      (node (ref "R2") (pin "2") (pinfunction "W_2") (pintype "passive"))
      (node (ref "U2") (pin "8") (pinfunction "CH7_8") (pintype "passive"))
    )
    (net (code "53") (name "Net-(U1-CH0)") (class "Default")
      (node (ref "R9") (pin "1") (pinfunction "1_1") (pintype "passive"))
      (node (ref "S8") (pin "1") (pinfunction "A_1") (pintype "passive"))
      (node (ref "S8") (pin "2") (pinfunction "A_2") (pintype "passive"))
      (node (ref "U1") (pin "1") (pinfunction "CH0_1") (pintype "passive"))
    )
    (net (code "54") (name "Net-(U1-CH1)") (class "Default")
      (node (ref "R10") (pin "1") (pinfunction "1_1") (pintype "passive"))
      (node (ref "S7") (pin "1") (pinfunction "A_1") (pintype "passive"))
      (node (ref "S7") (pin "2") (pinfunction "A_2") (pintype "passive"))
      (node (ref "U1") (pin "2") (pinfunction "CH1_2") (pintype "passive"))
    )
    (net (code "55") (name "Net-(U1-CH2)") (class "Default")
      (node (ref "R8") (pin "1") (pinfunction "1_1") (pintype "passive"))
      (node (ref "S6") (pin "1") (pinfunction "A_1") (pintype "passive"))
      (node (ref "S6") (pin "2") (pinfunction "A_2") (pintype "passive"))
      (node (ref "U1") (pin "3") (pinfunction "CH2_3") (pintype "passive"))
    )
    (net (code "56") (name "Net-(U1-CH3)") (class "Default")
      (node (ref "R7") (pin "1") (pinfunction "1_1") (pintype "passive"))
      (node (ref "S5") (pin "1") (pinfunction "A_1") (pintype "passive"))
      (node (ref "S5") (pin "2") (pinfunction "A_2") (pintype "passive"))
      (node (ref "U1") (pin "4") (pinfunction "CH3_4") (pintype "passive"))
    )
    (net (code "57") (name "Net-(U1-CH4)") (class "Default")
      (node (ref "R6") (pin "1") (pinfunction "1_1") (pintype "passive"))
      (node (ref "S4") (pin "1") (pinfunction "A_1") (pintype "passive"))
      (node (ref "S4") (pin "2") (pinfunction "A_2") (pintype "passive"))
      (node (ref "U1") (pin "5") (pinfunction "CH4_5") (pintype "passive"))
    )
    (net (code "58") (name "Net-(U1-CH5)") (class "Default")
      (node (ref "R5") (pin "1") (pinfunction "1_1") (pintype "passive"))
      (node (ref "S3") (pin "1") (pinfunction "A_1") (pintype "passive"))
      (node (ref "S3") (pin "2") (pinfunction "A_2") (pintype "passive"))
      (node (ref "U1") (pin "6") (pinfunction "CH5_6") (pintype "passive"))
    )
    (net (code "59") (name "Net-(U1-CH6)") (class "Default")
      (node (ref "R4") (pin "1") (pinfunction "1_1") (pintype "passive"))
      (node (ref "S2") (pin "1") (pinfunction "A_1") (pintype "passive"))
      (node (ref "S2") (pin "2") (pinfunction "A_2") (pintype "passive"))
      (node (ref "U1") (pin "7") (pinfunction "CH6_7") (pintype "passive"))
    )
    (net (code "60") (name "Net-(U1-CH7)") (class "Default")
      (node (ref "R3") (pin "1") (pinfunction "1_1") (pintype "passive"))
      (node (ref "S1") (pin "1") (pinfunction "A_1") (pintype "passive"))
      (node (ref "S1") (pin "2") (pinfunction "A_2") (pintype "passive"))
      (node (ref "U1") (pin "8") (pinfunction "CH7_8") (pintype "passive"))
    )
    (net (code "61") (name "Net-(U2-CH0)") (class "Default")
      (node (ref "R16") (pin "1") (pinfunction "1_1") (pintype "passive"))
      (node (ref "S14") (pin "1") (pinfunction "A_1") (pintype "passive"))
      (node (ref "S14") (pin "2") (pinfunction "A_2") (pintype "passive"))
      (node (ref "U2") (pin "1") (pinfunction "CH0_1") (pintype "passive"))
    )
    (net (code "62") (name "Net-(U2-CH1)") (class "Default")
      (node (ref "R15") (pin "1") (pinfunction "1_1") (pintype "passive"))
      (node (ref "S13") (pin "1") (pinfunction "A_1") (pintype "passive"))
      (node (ref "S13") (pin "2") (pinfunction "A_2") (pintype "passive"))
      (node (ref "U2") (pin "2") (pinfunction "CH1_2") (pintype "passive"))
    )
    (net (code "63") (name "Net-(U2-CH2)") (class "Default")
      (node (ref "R14") (pin "1") (pinfunction "1_1") (pintype "passive"))
      (node (ref "S12") (pin "1") (pinfunction "A_1") (pintype "passive"))
      (node (ref "S12") (pin "2") (pinfunction "A_2") (pintype "passive"))
      (node (ref "U2") (pin "3") (pinfunction "CH2_3") (pintype "passive"))
    )
    (net (code "64") (name "Net-(U2-CH3)") (class "Default")
      (node (ref "R13") (pin "1") (pinfunction "1_1") (pintype "passive"))
      (node (ref "S11") (pin "1") (pinfunction "A_1") (pintype "passive"))
      (node (ref "S11") (pin "2") (pinfunction "A_2") (pintype "passive"))
      (node (ref "U2") (pin "4") (pinfunction "CH3_4") (pintype "passive"))
    )
    (net (code "65") (name "Net-(U2-CH4)") (class "Default")
      (node (ref "R12") (pin "1") (pinfunction "1_1") (pintype "passive"))
      (node (ref "S10") (pin "1") (pinfunction "A_1") (pintype "passive"))
      (node (ref "S10") (pin "2") (pinfunction "A_2") (pintype "passive"))
      (node (ref "U2") (pin "5") (pinfunction "CH4_5") (pintype "passive"))
    )
    (net (code "66") (name "Net-(U2-CH5)") (class "Default")
      (node (ref "R11") (pin "1") (pinfunction "1_1") (pintype "passive"))
      (node (ref "S9") (pin "1") (pinfunction "A_1") (pintype "passive"))
      (node (ref "S9") (pin "2") (pinfunction "A_2") (pintype "passive"))
      (node (ref "U2") (pin "6") (pinfunction "CH5_6") (pintype "passive"))
    )
    (net (code "67") (name "Net-(U3-CH0)") (class "Default")
      (node (ref "R29") (pin "1") (pinfunction "1_1") (pintype "passive"))
      (node (ref "S23") (pin "1") (pinfunction "A_1") (pintype "passive"))
      (node (ref "S23") (pin "2") (pinfunction "A_2") (pintype "passive"))
      (node (ref "U3") (pin "1") (pinfunction "CH0_1") (pintype "passive"))
    )
    (net (code "68") (name "Net-(U3-CH1)") (class "Default")
      (node (ref "R30") (pin "1") (pinfunction "1_1") (pintype "passive"))
      (node (ref "S22") (pin "1") (pinfunction "A_1") (pintype "passive"))
      (node (ref "S22") (pin "2") (pinfunction "A_2") (pintype "passive"))
      (node (ref "U3") (pin "2") (pinfunction "CH1_2") (pintype "passive"))
    )
    (net (code "69") (name "Net-(U3-CH2)") (class "Default")
      (node (ref "R31") (pin "1") (pinfunction "1_1") (pintype "passive"))
      (node (ref "S21") (pin "1") (pinfunction "A_1") (pintype "passive"))
      (node (ref "S21") (pin "2") (pinfunction "A_2") (pintype "passive"))
      (node (ref "U3") (pin "3") (pinfunction "CH2_3") (pintype "passive"))
    )
    (net (code "70") (name "Net-(U3-CH3)") (class "Default")
      (node (ref "R32") (pin "1") (pinfunction "1_1") (pintype "passive"))
      (node (ref "S20") (pin "1") (pinfunction "A_1") (pintype "passive"))
      (node (ref "S20") (pin "2") (pinfunction "A_2") (pintype "passive"))
      (node (ref "U3") (pin "4") (pinfunction "CH3_4") (pintype "passive"))
    )
    (net (code "71") (name "Net-(U3-CH4)") (class "Default")
      (node (ref "R33") (pin "1") (pinfunction "1_1") (pintype "passive"))
      (node (ref "S19") (pin "1") (pinfunction "A_1") (pintype "passive"))
      (node (ref "S19") (pin "2") (pinfunction "A_2") (pintype "passive"))
      (node (ref "U3") (pin "5") (pinfunction "CH4_5") (pintype "passive"))
    )
    (net (code "72") (name "Net-(U3-CH5)") (class "Default")
      (node (ref "R34") (pin "1") (pinfunction "1_1") (pintype "passive"))
      (node (ref "S18") (pin "1") (pinfunction "A_1") (pintype "passive"))
      (node (ref "S18") (pin "2") (pinfunction "A_2") (pintype "passive"))
      (node (ref "U3") (pin "6") (pinfunction "CH5_6") (pintype "passive"))
    )
    (net (code "73") (name "Net-(U3-CH6)") (class "Default")
      (node (ref "R35") (pin "1") (pinfunction "1_1") (pintype "passive"))
      (node (ref "S17") (pin "1") (pinfunction "A_1") (pintype "passive"))
      (node (ref "S17") (pin "2") (pinfunction "A_2") (pintype "passive"))
      (node (ref "U3") (pin "7") (pinfunction "CH6_7") (pintype "passive"))
    )
    (net (code "74") (name "Net-(U3-CH7)") (class "Default")
      (node (ref "R36") (pin "1") (pinfunction "1_1") (pintype "passive"))
      (node (ref "S16") (pin "1") (pinfunction "A_1") (pintype "passive"))
      (node (ref "S16") (pin "2") (pinfunction "A_2") (pintype "passive"))
      (node (ref "U3") (pin "8") (pinfunction "CH7_8") (pintype "passive"))
    )
    (net (code "75") (name "VCC12_IN") (class "Default")
      (node (ref "ACCUM") (pin "2") (pinfunction "1_2") (pintype "passive"))
      (node (ref "Q1") (pin "3") (pinfunction "S_3") (pintype "passive"))
      (node (ref "R26") (pin "2") (pinfunction "2_2") (pintype "passive"))
      (node (ref "R27") (pin "2") (pinfunction "2_2") (pintype "passive"))
      (node (ref "T1") (pin "LCP") (pinfunction "P2_LCP") (pintype "passive"))
    )
    (net (code "76") (name "unconnected-(ESP-8266-GPIO0-Pad3)") (class "Default")
      (node (ref "ESP-8266") (pin "3") (pinfunction "GPIO0_3") (pintype "passive"))
    )
    (net (code "77") (name "unconnected-(ESP-8266-GPIO2-Pad2)") (class "Default")
      (node (ref "ESP-8266") (pin "2") (pinfunction "GPIO2_2") (pintype "passive"))
    )
    (net (code "78") (name "unconnected-(ESP-8266-GPIO16-Pad7)") (class "Default")
      (node (ref "ESP-8266") (pin "7") (pinfunction "GPIO16_7") (pintype "passive"))
    )
    (net (code "79") (name "unconnected-(J2-CD{slash}DAT3-Pad1)") (class "Default")
      (node (ref "J2") (pin "1") (pinfunction "CD/DAT3_1") (pintype "passive"))
    )
    (net (code "80") (name "unconnected-(J2-DAT1-Pad8)") (class "Default")
      (node (ref "J2") (pin "8") (pinfunction "DAT1_8") (pintype "passive"))
    )
    (net (code "81") (name "unconnected-(LCD-MODULE-NC-Pad23)") (class "Default")
      (node (ref "LCD-MODULE") (pin "23") (pinfunction "NC_23") (pintype "passive"))
    )
    (net (code "82") (name "unconnected-(LCD-MODULE-NC-Pad24)") (class "Default")
      (node (ref "LCD-MODULE") (pin "24") (pinfunction "NC_24") (pintype "passive"))
    )
    (net (code "83") (name "unconnected-(LCD-MODULE-NC-Pad25)") (class "Default")
      (node (ref "LCD-MODULE") (pin "25") (pinfunction "NC_25") (pintype "passive"))
    )
    (net (code "84") (name "unconnected-(LCD-MODULE-NC-Pad27)") (class "Default")
      (node (ref "LCD-MODULE") (pin "27") (pinfunction "NC_27") (pintype "passive"))
    )
    (net (code "85") (name "unconnected-(LCD-MODULE-NC-Pad28)") (class "Default")
      (node (ref "LCD-MODULE") (pin "28") (pinfunction "NC_28") (pintype "passive"))
    )
    (net (code "86") (name "unconnected-(LCD-MODULE-NC-Pad29)") (class "Default")
      (node (ref "LCD-MODULE") (pin "29") (pinfunction "NC_29") (pintype "passive"))
    )
    (net (code "87") (name "unconnected-(LCD-MODULE-NC-Pad30)") (class "Default")
      (node (ref "LCD-MODULE") (pin "30") (pinfunction "NC_30") (pintype "passive"))
    )
    (net (code "88") (name "unconnected-(LCD-MODULE-RESET-Pad37)") (class "Default")
      (node (ref "LCD-MODULE") (pin "37") (pinfunction "RESET_37") (pintype "passive"))
    )
    (net (code "89") (name "unconnected-(LCD-MODULE-SD_CLK-Pad33)") (class "Default")
      (node (ref "LCD-MODULE") (pin "33") (pinfunction "SD_CLK_33") (pintype "passive"))
    )
    (net (code "90") (name "unconnected-(LCD-MODULE-SD_CS-Pad34)") (class "Default")
      (node (ref "LCD-MODULE") (pin "34") (pinfunction "SD_CS_34") (pintype "passive"))
    )
    (net (code "91") (name "unconnected-(LCD-MODULE-SD_MISO-Pad31)") (class "Default")
      (node (ref "LCD-MODULE") (pin "31") (pinfunction "SD_MISO_31") (pintype "passive"))
    )
    (net (code "92") (name "unconnected-(LCD-MODULE-SD_MOSI-Pad32)") (class "Default")
      (node (ref "LCD-MODULE") (pin "32") (pinfunction "SD_MOSI_32") (pintype "passive"))
    )
  )
)
